# kardio.net
KiCad netlist of a schematic drawn in Altium Designer
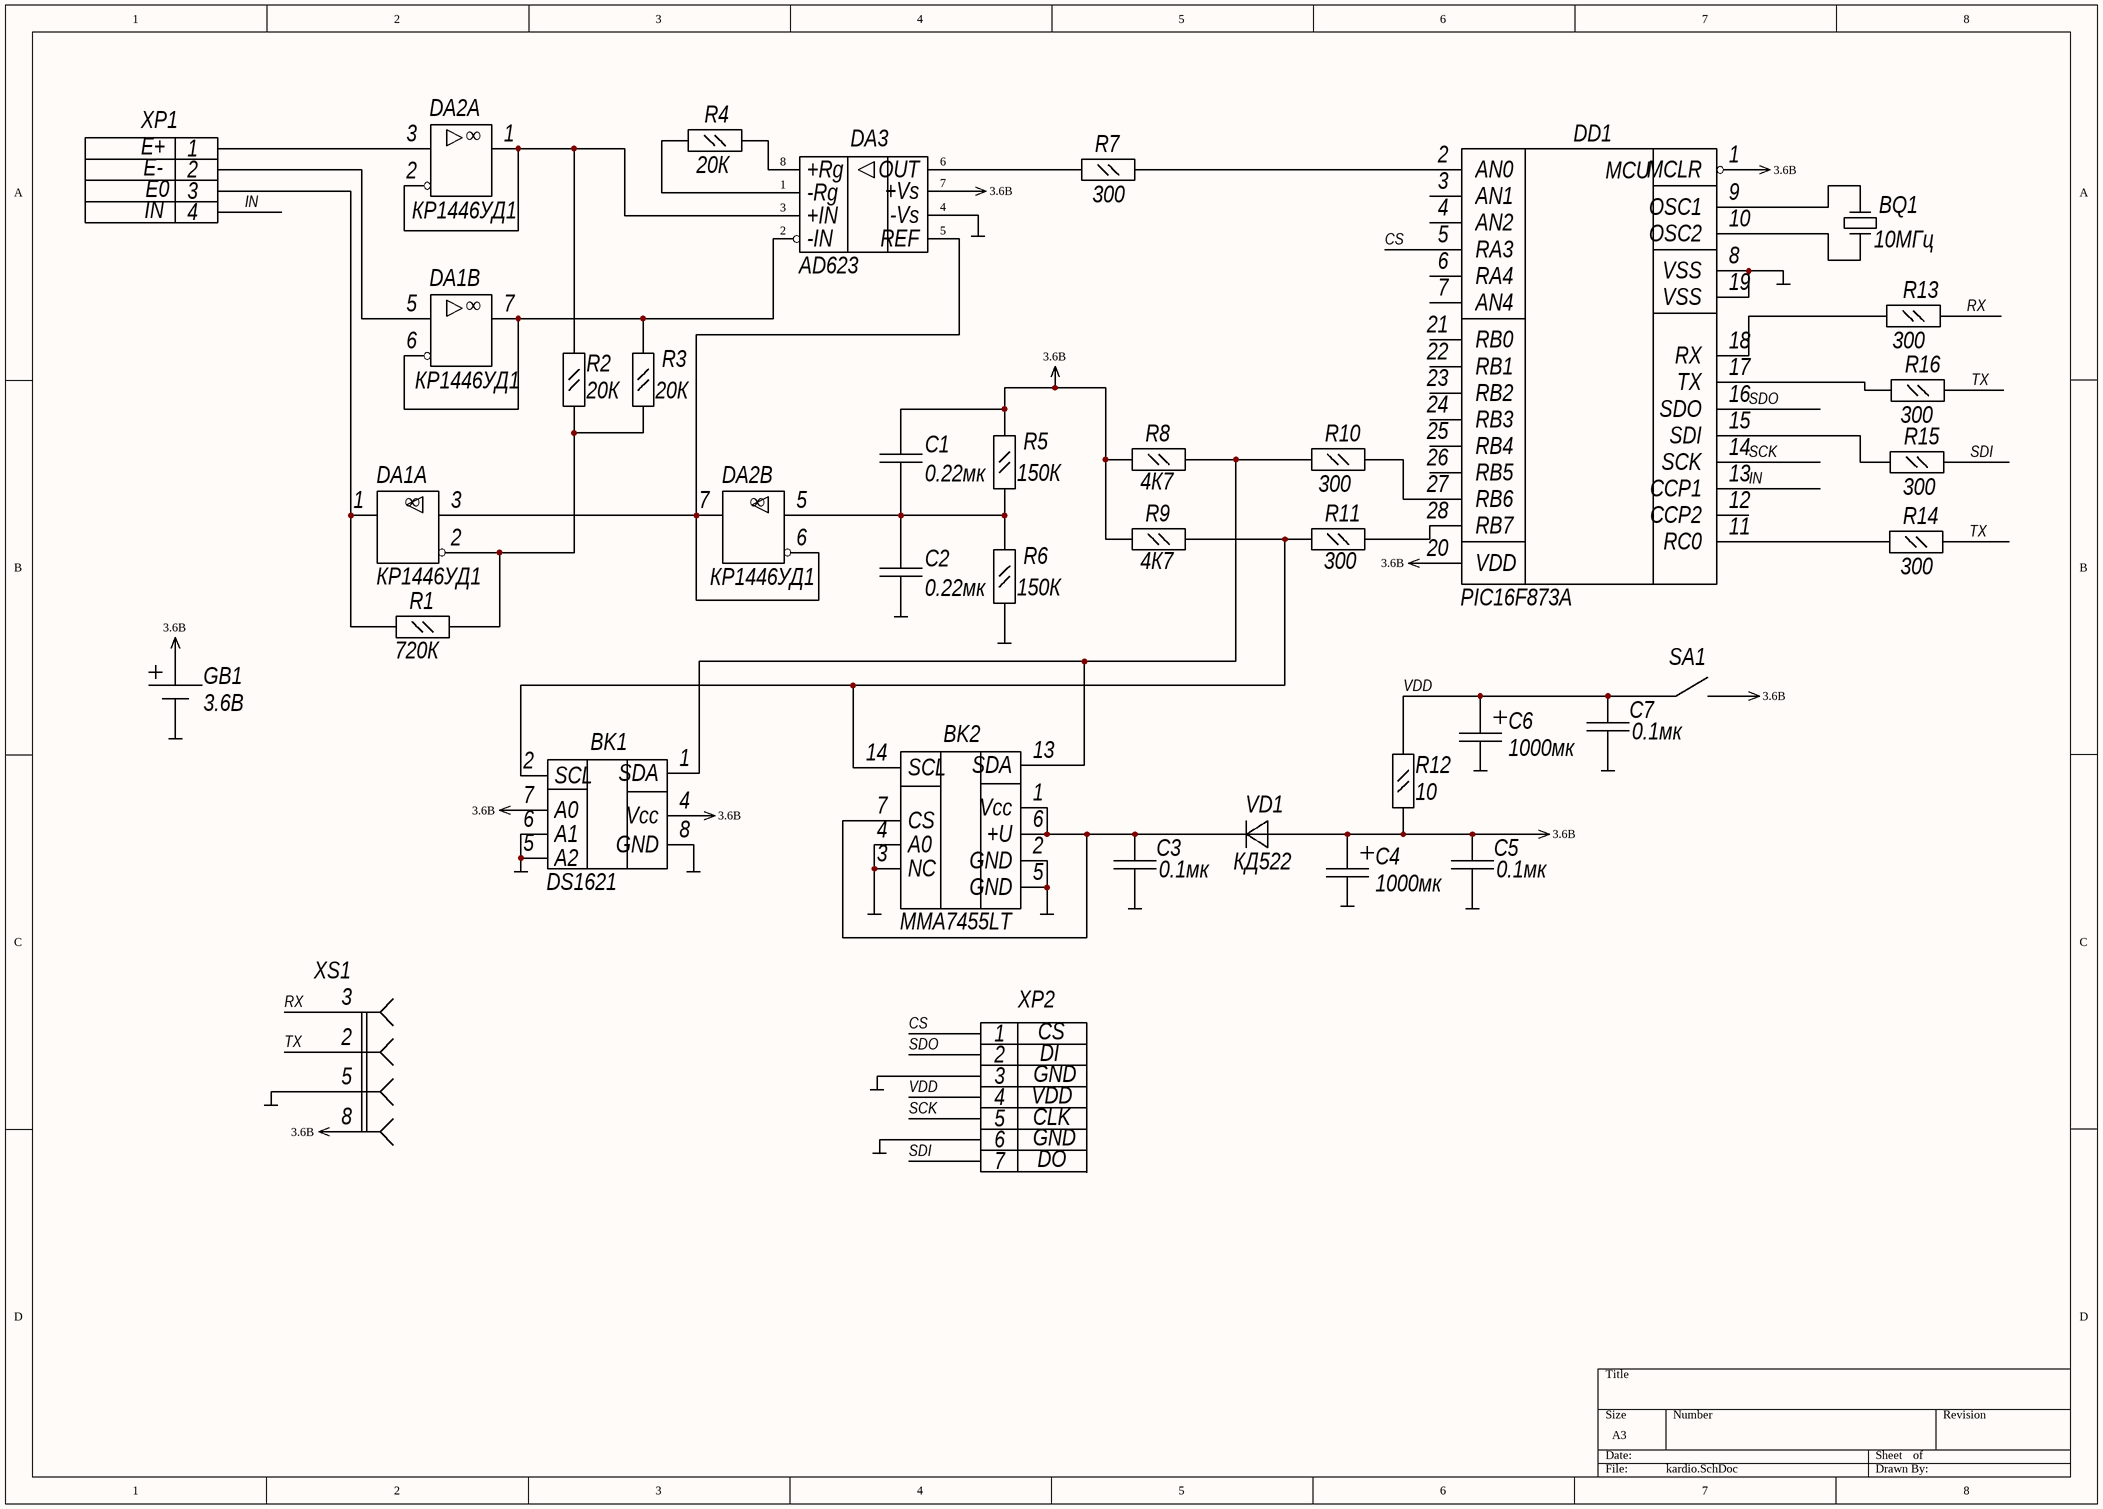
[diagram p0: kardio.SchDoc]

(export (version "E")
  (design (tool "Eeschema 10.0.6"))
  (components
    (comp (ref "BK1")
      (value "DS1621")
      (footprint "SOIC-8CM")
      (description "Temperature sensor")
      (libsource (lib "crdio_schlib") (part "DS1621"))
    )
    (comp (ref "BK2")
      (value "MMA7455LT")
      (footprint "SOJ80P300X0-12M")
      (description "Digital Output Accelerometer")
      (libsource (lib "crdio_schlib") (part "MMA7455LT"))
    )
    (comp (ref "BQ1")
      (value "10МГц")
      (footprint "HC49S")
      (libsource (lib "crdio_schlib") (part "Cristal Oscilator"))
    )
    (comp (ref "C1")
      (value "0.22мк")
      (footprint "C0805")
      (libsource (lib "crdio_schlib") (part "Capasitior"))
    )
    (comp (ref "C2")
      (value "0.22мк")
      (footprint "C0805")
      (libsource (lib "crdio_schlib") (part "Capasitior"))
    )
    (comp (ref "C3") (value "0.1мк") (footprint "C0805") (libsource (lib "crdio_schlib") (part "Capasitior")))
    (comp (ref "C4")
      (value "1000мк")
      (footprint "LZ 12x26 1000 мкФ x 25 В")
      (libsource (lib "crdio_schlib") (part "Capasitor electrolit"))
    )
    (comp (ref "C5") (value "0.1мк") (footprint "C0805") (libsource (lib "crdio_schlib") (part "Capasitior")))
    (comp (ref "C6")
      (value "1000мк")
      (footprint "LZ 12x26 1000 мкФ x 25 В")
      (libsource (lib "") (part "Capasitor electrolit_1"))
    )
    (comp (ref "C7") (value "0.1мк") (footprint "C0805") (libsource (lib "crdio_schlib") (part "Capasitior")))
    (comp (ref "DA1")
      (value "КР1446УД1")
      (footprint "PDIP8")
      (libsource (lib "crdio_schlib") (part "КР1446УД1"))
    )
    (comp (ref "DA2")
      (value "КР1446УД1")
      (footprint "PDIP8")
      (libsource (lib "crdio_schlib") (part "КР1446УД1"))
    )
    (comp (ref "DA3")
      (value "AD623")
      (footprint "SOIC-8CM")
      (description "Amplifier")
      (libsource (lib "crdio_schlib") (part "AD623"))
    )
    (comp (ref "DD1")
      (value "PIC16F873A")
      (footprint "SOIC-SO28_M")
      (fields (field (name "PUBLISHER") "Altium Limited"))
      (libsource (lib "crdio_schlib") (part "PIC16F873A-I/SO"))
    )
    (comp (ref "GB1") (value "3.6B") (footprint "Button") (libsource (lib "crdio_schlib") (part "Batery")))
    (comp (ref "R1") (value "720К") (footprint "1206") (libsource (lib "crdio_schlib") (part "Resistor")))
    (comp (ref "R2") (value "20К") (footprint "1206") (libsource (lib "crdio_schlib") (part "Resistor")))
    (comp (ref "R3") (value "20К") (footprint "1206") (libsource (lib "crdio_schlib") (part "Resistor")))
    (comp (ref "R4") (value "20К") (footprint "1206") (libsource (lib "crdio_schlib") (part "Resistor")))
    (comp (ref "R5") (value "150К") (footprint "1206") (libsource (lib "crdio_schlib") (part "Resistor")))
    (comp (ref "R6") (value "150К") (footprint "1206") (libsource (lib "crdio_schlib") (part "Resistor")))
    (comp (ref "R7") (value "300") (footprint "1206") (libsource (lib "crdio_schlib") (part "Resistor")))
    (comp (ref "R8") (value "4К7") (footprint "1206") (libsource (lib "crdio_schlib") (part "Resistor")))
    (comp (ref "R9") (value "4К7") (footprint "1206") (libsource (lib "crdio_schlib") (part "Resistor")))
    (comp (ref "R10") (value "300") (footprint "1206") (libsource (lib "crdio_schlib") (part "Resistor")))
    (comp (ref "R11") (value "300") (footprint "1206") (libsource (lib "crdio_schlib") (part "Resistor")))
    (comp (ref "R12") (value "10") (footprint "1206") (libsource (lib "crdio_schlib") (part "Resistor")))
    (comp (ref "R13") (value "300") (footprint "1206") (libsource (lib "crdio_schlib") (part "Resistor")))
    (comp (ref "R14") (value "300") (footprint "1206") (libsource (lib "crdio_schlib") (part "Resistor")))
    (comp (ref "R15") (value "300") (footprint "1206") (libsource (lib "crdio_schlib") (part "Resistor")))
    (comp (ref "R16") (value "300") (footprint "1206") (libsource (lib "crdio_schlib") (part "Resistor")))
    (comp (ref "SA1") (value "Button") (footprint "Button") (libsource (lib "crdio_schlib") (part "Button")))
    (comp (ref "VD1") (value "КД522") (footprint "DO-41") (libsource (lib "crdio_schlib") (part "КД522")))
    (comp (ref "XP1")
      (value "INPUT")
      (footprint "HDR1X4 - WA")
      (libsource (lib "crdio_schlib") (part "INPUT"))
    )
    (comp (ref "XP2")
      (value "SD-card")
      (footprint "HDR2X4 - wide area")
      (libsource (lib "crdio_schlib") (part "SD-card"))
    )
    (comp (ref "XS1") (value "COM-port") (libsource (lib "crdio_schlib") (part "COM-port")))
  )
  (nets
    (net (code "1") (name "/CS") (class "Default")
      (node (ref "DD1") (pin "5") (pinfunction "RA3_5") (pintype "passive"))
      (node (ref "XP2") (pin "1") (pinfunction "1_1") (pintype "passive"))
    )
    (net (code "2") (name "/IN") (class "Default")
      (node (ref "DD1") (pin "13") (pinfunction "CCP1_13") (pintype "passive"))
      (node (ref "XP1") (pin "4") (pinfunction "4_4") (pintype "passive"))
    )
    (net (code "3") (name "/RX") (class "Default")
      (node (ref "R13") (pin "2") (pinfunction "2_2") (pintype "passive"))
      (node (ref "XS1") (pin "3") (pintype "passive"))
    )
    (net (code "4") (name "/SCK") (class "Default")
      (node (ref "DD1") (pin "14") (pinfunction "SCK_14") (pintype "passive"))
      (node (ref "XP2") (pin "5") (pinfunction "5_5") (pintype "passive"))
    )
    (net (code "5") (name "/SDI") (class "Default")
      (node (ref "R15") (pin "2") (pinfunction "2_2") (pintype "passive"))
      (node (ref "XP2") (pin "7") (pinfunction "7_7") (pintype "passive"))
    )
    (net (code "6") (name "/SDO") (class "Default")
      (node (ref "DD1") (pin "16") (pinfunction "SDO_16") (pintype "passive"))
      (node (ref "XP2") (pin "2") (pinfunction "2_2") (pintype "passive"))
    )
    (net (code "7") (name "/TX") (class "Default")
      (node (ref "R14") (pin "2") (pinfunction "2_2") (pintype "passive"))
      (node (ref "R16") (pin "2") (pinfunction "2_2") (pintype "passive"))
      (node (ref "XS1") (pin "2") (pintype "passive"))
    )
    (net (code "8") (name "/VDD") (class "Default")
      (node (ref "C6") (pin "1") (pintype "passive"))
      (node (ref "C7") (pin "1") (pintype "passive"))
      (node (ref "R12") (pin "2") (pinfunction "2_2") (pintype "passive"))
      (node (ref "SA1") (pin "1") (pintype "passive"))
      (node (ref "XP2") (pin "4") (pinfunction "4_4") (pintype "passive"))
    )
    (net (code "9") (name "3.6В") (class "Default")
      (node (ref "BK1") (pin "4") (pinfunction "Vcc_4") (pintype "passive"))
      (node (ref "BK1") (pin "7") (pinfunction "A0_7") (pintype "passive"))
      (node (ref "C1") (pin "2") (pintype "passive"))
      (node (ref "C4") (pin "1") (pintype "passive"))
      (node (ref "C5") (pin "1") (pintype "passive"))
      (node (ref "DA3") (pin "7") (pinfunction "+Vs_7") (pintype "passive"))
      (node (ref "DD1") (pin "1") (pinfunction "MCLR_1") (pintype "passive"))
      (node (ref "DD1") (pin "20") (pinfunction "VDD_20") (pintype "passive"))
      (node (ref "GB1") (pin "2") (pintype "passive"))
      (node (ref "R12") (pin "1") (pinfunction "1_1") (pintype "passive"))
      (node (ref "R5") (pin "2") (pinfunction "2_2") (pintype "passive"))
      (node (ref "R8") (pin "1") (pinfunction "1_1") (pintype "passive"))
      (node (ref "R9") (pin "1") (pinfunction "1_1") (pintype "passive"))
      (node (ref "SA1") (pin "2") (pintype "passive"))
      (node (ref "VD1") (pin "1") (pintype "passive"))
      (node (ref "XS1") (pin "8") (pintype "passive"))
    )
    (net (code "10") (name "GND") (class "Default")
      (node (ref "BK1") (pin "5") (pinfunction "A2_5") (pintype "passive"))
      (node (ref "BK1") (pin "6") (pinfunction "A1_6") (pintype "passive"))
      (node (ref "BK1") (pin "8") (pinfunction "GND_8") (pintype "passive"))
      (node (ref "BK2") (pin "2") (pinfunction "GND_2") (pintype "passive"))
      (node (ref "BK2") (pin "3") (pinfunction "NC_3") (pintype "passive"))
      (node (ref "BK2") (pin "4") (pinfunction "A0_4") (pintype "passive"))
      (node (ref "BK2") (pin "5") (pinfunction "GND_5") (pintype "passive"))
      (node (ref "C2") (pin "1") (pintype "passive"))
      (node (ref "C3") (pin "2") (pintype "passive"))
      (node (ref "C4") (pin "2") (pintype "passive"))
      (node (ref "C5") (pin "2") (pintype "passive"))
      (node (ref "C6") (pin "2") (pintype "passive"))
      (node (ref "C7") (pin "2") (pintype "passive"))
      (node (ref "DA3") (pin "4") (pinfunction "-Vs_4") (pintype "passive"))
      (node (ref "DD1") (pin "19") (pinfunction "VSS_19") (pintype "passive"))
      (node (ref "DD1") (pin "8") (pinfunction "VSS_8") (pintype "passive"))
      (node (ref "GB1") (pin "1") (pintype "passive"))
      (node (ref "R6") (pin "1") (pinfunction "1_1") (pintype "passive"))
      (node (ref "XP2") (pin "3") (pinfunction "3_3") (pintype "passive"))
      (node (ref "XP2") (pin "6") (pinfunction "6_6") (pintype "passive"))
      (node (ref "XS1") (pin "5") (pintype "passive"))
    )
    (net (code "11") (name "Net-(BK1-SCL)") (class "Default")
      (node (ref "BK1") (pin "2") (pinfunction "SCL_2") (pintype "passive"))
      (node (ref "BK2") (pin "14") (pinfunction "SCL_14") (pintype "passive"))
      (node (ref "R11") (pin "1") (pinfunction "1_1") (pintype "passive"))
      (node (ref "R9") (pin "2") (pinfunction "2_2") (pintype "passive"))
    )
    (net (code "12") (name "Net-(BK1-SDA)") (class "Default")
      (node (ref "BK1") (pin "1") (pinfunction "SDA_1") (pintype "passive"))
      (node (ref "BK2") (pin "13") (pinfunction "SDA_13") (pintype "passive"))
      (node (ref "R10") (pin "1") (pinfunction "1_1") (pintype "passive"))
      (node (ref "R8") (pin "2") (pinfunction "2_2") (pintype "passive"))
    )
    (net (code "13") (name "Net-(BK2-+U)") (class "Default")
      (node (ref "BK2") (pin "1") (pinfunction "Vcc_1") (pintype "passive"))
      (node (ref "BK2") (pin "6") (pinfunction "+U_6") (pintype "passive"))
      (node (ref "BK2") (pin "7") (pinfunction "CS_7") (pintype "passive"))
      (node (ref "C3") (pin "1") (pintype "passive"))
      (node (ref "VD1") (pin "2") (pintype "passive"))
    )
    (net (code "14") (name "Net-(DA1-Pad1)") (class "Default")
      (node (ref "DA1") (pin "1") (pinfunction "1_1") (pintype "passive"))
      (node (ref "R1") (pin "1") (pinfunction "1_1") (pintype "passive"))
      (node (ref "XP1") (pin "3") (pinfunction "3_3") (pintype "passive"))
    )
    (net (code "15") (name "Net-(DA1-Pad2)") (class "Default")
      (node (ref "DA1") (pin "2") (pinfunction "2_2") (pintype "power_in"))
      (node (ref "R1") (pin "2") (pinfunction "2_2") (pintype "passive"))
      (node (ref "R2") (pin "1") (pinfunction "1_1") (pintype "passive"))
      (node (ref "R3") (pin "1") (pinfunction "1_1") (pintype "passive"))
    )
    (net (code "16") (name "Net-(DA1B-1)") (class "Default")
      (node (ref "DA1") (pin "6") (pinfunction "2_6") (pintype "power_in"))
      (node (ref "DA1") (pin "7") (pinfunction "1_7") (pintype "passive"))
      (node (ref "DA3") (pin "2") (pinfunction "-IN_2") (pintype "passive"))
      (node (ref "R3") (pin "2") (pinfunction "2_2") (pintype "passive"))
    )
    (net (code "17") (name "Net-(DA1B-3)") (class "Default")
      (node (ref "DA1") (pin "5") (pinfunction "3_5") (pintype "passive"))
      (node (ref "XP1") (pin "2") (pinfunction "2_2") (pintype "passive"))
    )
    (net (code "18") (name "Net-(DA2-Pad3)") (class "Default")
      (node (ref "DA2") (pin "3") (pinfunction "3_3") (pintype "passive"))
      (node (ref "XP1") (pin "1") (pinfunction "1_1") (pintype "passive"))
    )
    (net (code "19") (name "Net-(DA2B-1)") (class "Default")
      (node (ref "DA1") (pin "3") (pinfunction "3_3") (pintype "passive"))
      (node (ref "DA2") (pin "6") (pinfunction "2_6") (pintype "power_in"))
      (node (ref "DA2") (pin "7") (pinfunction "1_7") (pintype "passive"))
      (node (ref "DA3") (pin "5") (pinfunction "REF_5") (pintype "passive"))
    )
    (net (code "20") (name "Net-(DA2B-3)") (class "Default")
      (node (ref "C1") (pin "1") (pintype "passive"))
      (node (ref "C2") (pin "2") (pintype "passive"))
      (node (ref "DA2") (pin "5") (pinfunction "3_5") (pintype "passive"))
      (node (ref "R5") (pin "1") (pinfunction "1_1") (pintype "passive"))
      (node (ref "R6") (pin "2") (pinfunction "2_2") (pintype "passive"))
    )
    (net (code "21") (name "Net-(DA3-+IN)") (class "Default")
      (node (ref "DA2") (pin "1") (pinfunction "1_1") (pintype "passive"))
      (node (ref "DA2") (pin "2") (pinfunction "2_2") (pintype "power_in"))
      (node (ref "DA3") (pin "3") (pinfunction "+IN_3") (pintype "passive"))
      (node (ref "R2") (pin "2") (pinfunction "2_2") (pintype "passive"))
    )
    (net (code "22") (name "Net-(DA3-+Rg)") (class "Default")
      (node (ref "DA3") (pin "8") (pinfunction "+Rg_8") (pintype "passive"))
      (node (ref "R4") (pin "1") (pinfunction "1_1") (pintype "passive"))
    )
    (net (code "23") (name "Net-(DA3--Rg)") (class "Default")
      (node (ref "DA3") (pin "1") (pinfunction "-Rg_1") (pintype "passive"))
      (node (ref "R4") (pin "2") (pinfunction "2_2") (pintype "passive"))
    )
    (net (code "24") (name "Net-(DA3-OUT)") (class "Default")
      (node (ref "DA3") (pin "6") (pinfunction "OUT_6") (pintype "passive"))
      (node (ref "R7") (pin "1") (pinfunction "1_1") (pintype "passive"))
    )
    (net (code "25") (name "Net-(DD1-AN0)") (class "Default")
      (node (ref "DD1") (pin "2") (pinfunction "AN0_2") (pintype "passive"))
      (node (ref "R7") (pin "2") (pinfunction "2_2") (pintype "passive"))
    )
    (net (code "26") (name "Net-(DD1-OSC1)") (class "Default")
      (node (ref "BQ1") (pin "2") (pintype "passive"))
      (node (ref "DD1") (pin "9") (pinfunction "OSC1_9") (pintype "passive"))
    )
    (net (code "27") (name "Net-(DD1-OSC2)") (class "Default")
      (node (ref "BQ1") (pin "1") (pintype "passive"))
      (node (ref "DD1") (pin "10") (pinfunction "OSC2_10") (pintype "passive"))
    )
    (net (code "28") (name "Net-(DD1-RB6)") (class "Default")
      (node (ref "DD1") (pin "27") (pinfunction "RB6_27") (pintype "passive"))
      (node (ref "R10") (pin "2") (pinfunction "2_2") (pintype "passive"))
    )
    (net (code "29") (name "Net-(DD1-RB7)") (class "Default")
      (node (ref "DD1") (pin "28") (pinfunction "RB7_28") (pintype "passive"))
      (node (ref "R11") (pin "2") (pinfunction "2_2") (pintype "passive"))
    )
    (net (code "30") (name "Net-(DD1-RC0)") (class "Default")
      (node (ref "DD1") (pin "11") (pinfunction "RC0_11") (pintype "passive"))
      (node (ref "R14") (pin "1") (pinfunction "1_1") (pintype "passive"))
    )
    (net (code "31") (name "Net-(DD1-RX)") (class "Default")
      (node (ref "DD1") (pin "18") (pinfunction "RX_18") (pintype "passive"))
      (node (ref "R13") (pin "1") (pinfunction "1_1") (pintype "passive"))
    )
    (net (code "32") (name "Net-(DD1-SDI)") (class "Default")
      (node (ref "DD1") (pin "15") (pinfunction "SDI_15") (pintype "passive"))
      (node (ref "R15") (pin "1") (pinfunction "1_1") (pintype "passive"))
    )
    (net (code "33") (name "Net-(DD1-TX)") (class "Default")
      (node (ref "DD1") (pin "17") (pinfunction "TX_17") (pintype "passive"))
      (node (ref "R16") (pin "1") (pinfunction "1_1") (pintype "passive"))
    )
    (net (code "34") (name "unconnected-(DD1-AN1-Pad3)") (class "Default")
      (node (ref "DD1") (pin "3") (pinfunction "AN1_3") (pintype "passive"))
    )
    (net (code "35") (name "unconnected-(DD1-AN2-Pad4)") (class "Default")
      (node (ref "DD1") (pin "4") (pinfunction "AN2_4") (pintype "passive"))
    )
    (net (code "36") (name "unconnected-(DD1-AN4-Pad7)") (class "Default")
      (node (ref "DD1") (pin "7") (pinfunction "AN4_7") (pintype "passive"))
    )
    (net (code "37") (name "unconnected-(DD1-CCP2-Pad12)") (class "Default")
      (node (ref "DD1") (pin "12") (pinfunction "CCP2_12") (pintype "passive"))
    )
    (net (code "38") (name "unconnected-(DD1-RA4-Pad6)") (class "Default")
      (node (ref "DD1") (pin "6") (pinfunction "RA4_6") (pintype "passive"))
    )
    (net (code "39") (name "unconnected-(DD1-RB0-Pad21)") (class "Default")
      (node (ref "DD1") (pin "21") (pinfunction "RB0_21") (pintype "passive"))
    )
    (net (code "40") (name "unconnected-(DD1-RB1-Pad22)") (class "Default")
      (node (ref "DD1") (pin "22") (pinfunction "RB1_22") (pintype "passive"))
    )
    (net (code "41") (name "unconnected-(DD1-RB2-Pad23)") (class "Default")
      (node (ref "DD1") (pin "23") (pinfunction "RB2_23") (pintype "passive"))
    )
    (net (code "42") (name "unconnected-(DD1-RB3-Pad24)") (class "Default")
      (node (ref "DD1") (pin "24") (pinfunction "RB3_24") (pintype "passive"))
    )
    (net (code "43") (name "unconnected-(DD1-RB4-Pad25)") (class "Default")
      (node (ref "DD1") (pin "25") (pinfunction "RB4_25") (pintype "passive"))
    )
    (net (code "44") (name "unconnected-(DD1-RB5-Pad26)") (class "Default")
      (node (ref "DD1") (pin "26") (pinfunction "RB5_26") (pintype "passive"))
    )
  )
)
